# 06_SOM_USB_CARD.net
KiCad netlist of a schematic drawn in Altium Designer
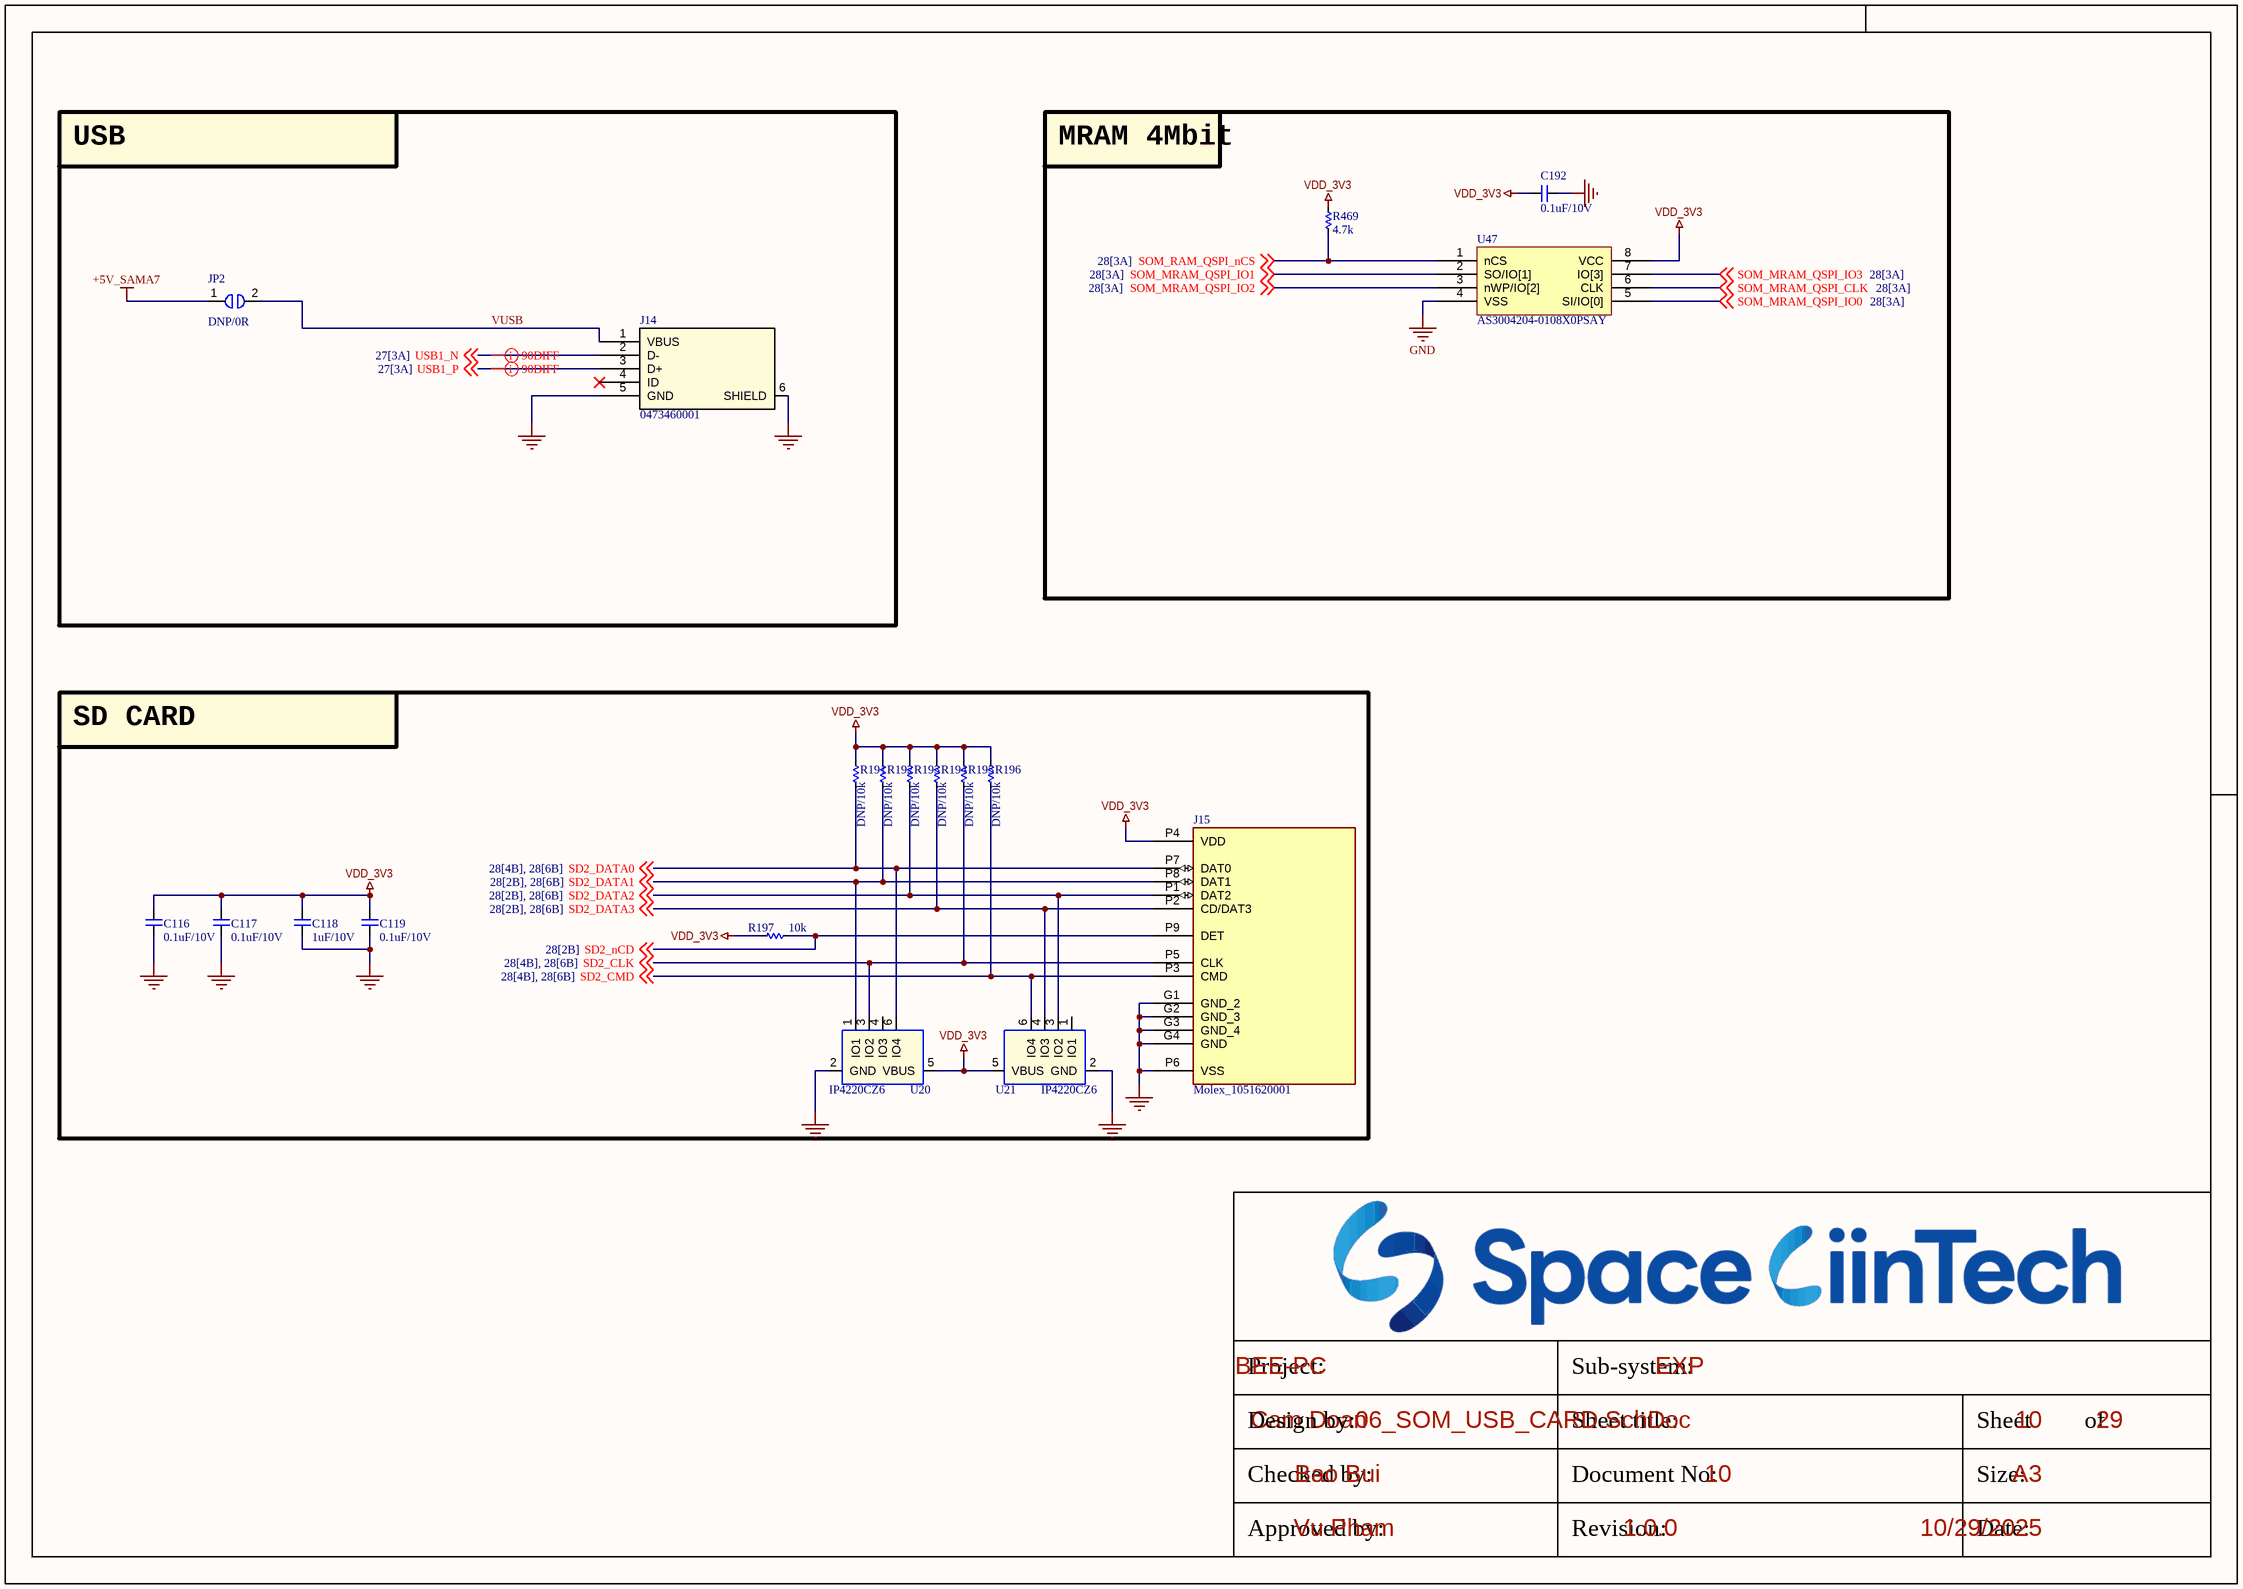
[diagram p0: 06_SOM_USB_CARD.SchDoc]

(export (version "E")
  (design (tool "Eeschema 10.0.6"))
  (components
    (comp (ref "C116")
      (value "0.1uF/10V")
      (footprint "CAP_C_1005X60")
      (description "CAP CHIP")
      (libsource (lib "LABLIB") (part "_CAP_C_2"))
    )
    (comp (ref "C117")
      (value "0.1uF/10V")
      (footprint "CAP_C_1005X60")
      (description "CAP CHIP")
      (libsource (lib "LABLIB") (part "_CAP_C_2"))
    )
    (comp (ref "C118")
      (value "1uF/10V")
      (footprint "CAP_C_1005X60")
      (description "CAP CHIP")
      (libsource (lib "LABLIB") (part "_CAP_C_2"))
    )
    (comp (ref "C119")
      (value "0.1uF/10V")
      (footprint "CAP_C_1005X60")
      (description "CAP CHIP")
      (libsource (lib "LABLIB") (part "_CAP_C_2"))
    )
    (comp (ref "C192")
      (value "0.1uF/10V")
      (footprint "CAP_C_1005X60")
      (description "CAP CHIP")
      (libsource (lib "LABLIB") (part "_CAP_C_2"))
    )
    (comp (ref "J14")
      (value "0473460001")
      (footprint "47346-0001_MOL")
      (description "No Description Available")
      (libsource (lib "obc_ver2") (part "USB_micro"))
    )
    (comp (ref "J15")
      (value "Molex_1051620001")
      (footprint "Molex_1051620001")
      (description "9 (8 + 1) Position Card Connector Secure Digital - microSDâ„¢ Surface Mount, Right Angle Gold")
      (fields (field (name "MF") "Molex") (field (name "MP") "1051620001"))
      (libsource (lib "new_component") (part "Molex_1051620001"))
    )
    (comp (ref "JP2")
      (value "DNP/0R")
      (footprint "RES_C_1608X60")
      (libsource (lib "LABLIB") (part "JUMPER_1_1"))
    )
    (comp (ref "R191")
      (value "DNP/10k")
      (footprint "RES_C_1005X40")
      (description "RES")
      (libsource (lib "LABLIB") (part "_RES_B_2"))
    )
    (comp (ref "R192")
      (value "DNP/10k")
      (footprint "RES_C_1005X40")
      (description "RES")
      (libsource (lib "LABLIB") (part "_RES_B_2"))
    )
    (comp (ref "R193")
      (value "DNP/10k")
      (footprint "RES_C_1005X40")
      (description "RES")
      (libsource (lib "LABLIB") (part "_RES_B_2"))
    )
    (comp (ref "R194")
      (value "DNP/10k")
      (footprint "RES_C_1005X40")
      (description "RES")
      (libsource (lib "LABLIB") (part "_RES_B_2"))
    )
    (comp (ref "R195")
      (value "DNP/10k")
      (footprint "RES_C_1005X40")
      (description "RES")
      (libsource (lib "LABLIB") (part "_RES_B_2"))
    )
    (comp (ref "R196")
      (value "DNP/10k")
      (footprint "RES_C_1005X40")
      (description "RES")
      (libsource (lib "LABLIB") (part "_RES_B_2"))
    )
    (comp (ref "R197")
      (value "10k")
      (footprint "RES_C_1005X40")
      (description "RES")
      (libsource (lib "LABLIB") (part "_RES_B_2"))
    )
    (comp (ref "R469")
      (value "4.7k")
      (footprint "RES_C_1005X40")
      (description "RES")
      (libsource (lib "LABLIB") (part "_RES_B_2"))
    )
    (comp (ref "U20")
      (value "IP4220CZ6")
      (footprint "SOT95P280X145-6N")
      (libsource (lib "*") (part "IP4220CZ6_0"))
    )
    (comp (ref "U21")
      (value "IP4220CZ6")
      (footprint "SOT95P280X145-6N")
      (libsource (lib "") (part "IP4220CZ6_0_1"))
    )
    (comp (ref "U47")
      (value "AS3004204-0108X0PSAY")
      (footprint "SOIC127P790X216-8")
      (libsource (lib "LABLIB") (part "IC_RAM_AS3004204-0108X0PSAY"))
    )
  )
  (nets
    (net (code "1") (name "+5V_SAMA7") (class "Default")
      (node (ref "JP2") (pin "1") (pinfunction "1_1") (pintype "passive"))
    )
    (net (code "2") (name "/VUSB") (class "Default")
      (node (ref "J14") (pin "1") (pinfunction "VBUS_1") (pintype "passive"))
      (node (ref "JP2") (pin "2") (pinfunction "2_2") (pintype "passive"))
    )
    (net (code "3") (name "GND") (class "Default")
      (node (ref "C116") (pin "1") (pinfunction "1_1") (pintype "passive"))
      (node (ref "C117") (pin "1") (pinfunction "1_1") (pintype "passive"))
      (node (ref "C118") (pin "1") (pinfunction "1_1") (pintype "passive"))
      (node (ref "C119") (pin "1") (pinfunction "1_1") (pintype "passive"))
      (node (ref "C192") (pin "1") (pinfunction "1_1") (pintype "passive"))
      (node (ref "J14") (pin "5") (pinfunction "GND_5") (pintype "power_in"))
      (node (ref "J14") (pin "6") (pinfunction "SHIELD_6") (pintype "passive"))
      (node (ref "J15") (pin "G1") (pinfunction "GND_2_G1") (pintype "passive"))
      (node (ref "J15") (pin "G2") (pinfunction "GND_3_G2") (pintype "passive"))
      (node (ref "J15") (pin "G3") (pinfunction "GND_4_G3") (pintype "passive"))
      (node (ref "J15") (pin "G4") (pinfunction "GND_G4") (pintype "passive"))
      (node (ref "J15") (pin "P6") (pinfunction "VSS_P6") (pintype "passive"))
      (node (ref "U20") (pin "2") (pinfunction "GND_2") (pintype "passive"))
      (node (ref "U21") (pin "2") (pinfunction "GND_2") (pintype "passive"))
      (node (ref "U47") (pin "4") (pinfunction "VSS_4") (pintype "passive"))
    )
    (net (code "4") (name "SD2_CLK") (class "Default")
      (node (ref "J15") (pin "P5") (pinfunction "CLK_P5") (pintype "passive"))
      (node (ref "R195") (pin "1") (pinfunction "1_1") (pintype "passive"))
      (node (ref "U20") (pin "3") (pinfunction "IO2_3") (pintype "passive"))
    )
    (net (code "5") (name "SD2_CMD") (class "Default")
      (node (ref "J15") (pin "P3") (pinfunction "CMD_P3") (pintype "passive"))
      (node (ref "R196") (pin "1") (pinfunction "1_1") (pintype "passive"))
      (node (ref "U21") (pin "6") (pinfunction "IO4_6") (pintype "passive"))
    )
    (net (code "6") (name "SD2_DATA0") (class "Default")
      (node (ref "J15") (pin "P7") (pinfunction "DAT0_P7") (pintype "bidirectional"))
      (node (ref "R191") (pin "1") (pinfunction "1_1") (pintype "passive"))
      (node (ref "U20") (pin "6") (pinfunction "IO4_6") (pintype "passive"))
    )
    (net (code "7") (name "SD2_DATA1") (class "Default")
      (node (ref "J15") (pin "P8") (pinfunction "DAT1_P8") (pintype "bidirectional"))
      (node (ref "R192") (pin "1") (pinfunction "1_1") (pintype "passive"))
      (node (ref "U20") (pin "1") (pinfunction "IO1_1") (pintype "passive"))
    )
    (net (code "8") (name "SD2_DATA2") (class "Default")
      (node (ref "J15") (pin "P1") (pinfunction "DAT2_P1") (pintype "bidirectional"))
      (node (ref "R193") (pin "1") (pinfunction "1_1") (pintype "passive"))
      (node (ref "U21") (pin "3") (pinfunction "IO2_3") (pintype "passive"))
    )
    (net (code "9") (name "SD2_DATA3") (class "Default")
      (node (ref "J15") (pin "P2") (pinfunction "CD/DAT3_P2") (pintype "passive"))
      (node (ref "R194") (pin "1") (pinfunction "1_1") (pintype "passive"))
      (node (ref "U21") (pin "4") (pinfunction "IO3_4") (pintype "passive"))
    )
    (net (code "10") (name "SD2_nCD") (class "Default")
      (node (ref "J15") (pin "P9") (pinfunction "DET_P9") (pintype "passive"))
      (node (ref "R197") (pin "2") (pinfunction "2_2") (pintype "passive"))
    )
    (net (code "11") (name "SOM_MRAM_QSPI_CLK") (class "Default")
      (node (ref "U47") (pin "6") (pinfunction "CLK_6") (pintype "passive"))
    )
    (net (code "12") (name "SOM_MRAM_QSPI_IO0") (class "Default")
      (node (ref "U47") (pin "5") (pinfunction "SI/IO[0]_5") (pintype "passive"))
    )
    (net (code "13") (name "SOM_MRAM_QSPI_IO1") (class "Default")
      (node (ref "U47") (pin "2") (pinfunction "SO/IO[1]_2") (pintype "passive"))
    )
    (net (code "14") (name "SOM_MRAM_QSPI_IO2") (class "Default")
      (node (ref "U47") (pin "3") (pinfunction "nWP/IO[2]_3") (pintype "passive"))
    )
    (net (code "15") (name "SOM_MRAM_QSPI_IO3") (class "Default")
      (node (ref "U47") (pin "7") (pinfunction "IO[3]_7") (pintype "passive"))
    )
    (net (code "16") (name "SOM_RAM_QSPI_nCS") (class "Default")
      (node (ref "R469") (pin "1") (pinfunction "1_1") (pintype "passive"))
      (node (ref "U47") (pin "1") (pinfunction "nCS_1") (pintype "passive"))
    )
    (net (code "17") (name "USB1_N") (class "Default")
      (node (ref "J14") (pin "2") (pinfunction "D-_2") (pintype "passive"))
    )
    (net (code "18") (name "USB1_P") (class "Default")
      (node (ref "J14") (pin "3") (pinfunction "D+_3") (pintype "passive"))
    )
    (net (code "19") (name "VDD_3V3") (class "Default")
      (node (ref "C116") (pin "2") (pinfunction "2_2") (pintype "passive"))
      (node (ref "C117") (pin "2") (pinfunction "2_2") (pintype "passive"))
      (node (ref "C118") (pin "2") (pinfunction "2_2") (pintype "passive"))
      (node (ref "C119") (pin "2") (pinfunction "2_2") (pintype "passive"))
      (node (ref "C192") (pin "2") (pinfunction "2_2") (pintype "passive"))
      (node (ref "J15") (pin "P4") (pinfunction "VDD_P4") (pintype "power_in"))
      (node (ref "R191") (pin "2") (pinfunction "2_2") (pintype "passive"))
      (node (ref "R192") (pin "2") (pinfunction "2_2") (pintype "passive"))
      (node (ref "R193") (pin "2") (pinfunction "2_2") (pintype "passive"))
      (node (ref "R194") (pin "2") (pinfunction "2_2") (pintype "passive"))
      (node (ref "R195") (pin "2") (pinfunction "2_2") (pintype "passive"))
      (node (ref "R196") (pin "2") (pinfunction "2_2") (pintype "passive"))
      (node (ref "R197") (pin "1") (pinfunction "1_1") (pintype "passive"))
      (node (ref "R469") (pin "2") (pinfunction "2_2") (pintype "passive"))
      (node (ref "U20") (pin "5") (pinfunction "VBUS_5") (pintype "passive"))
      (node (ref "U21") (pin "5") (pinfunction "VBUS_5") (pintype "passive"))
      (node (ref "U47") (pin "8") (pinfunction "VCC_8") (pintype "passive"))
    )
    (net (code "20") (name "unconnected-(J14-ID-Pad4)") (class "Default")
      (node (ref "J14") (pin "4") (pinfunction "ID_4") (pintype "passive+no_connect"))
    )
    (net (code "21") (name "unconnected-(U20-IO3-Pad4)") (class "Default")
      (node (ref "U20") (pin "4") (pinfunction "IO3_4") (pintype "passive"))
    )
    (net (code "22") (name "unconnected-(U21-IO1-Pad1)") (class "Default")
      (node (ref "U21") (pin "1") (pinfunction "IO1_1") (pintype "passive"))
    )
  )
)
